# PowerDelivery.net
KiCad netlist of a schematic drawn in Altium Designer
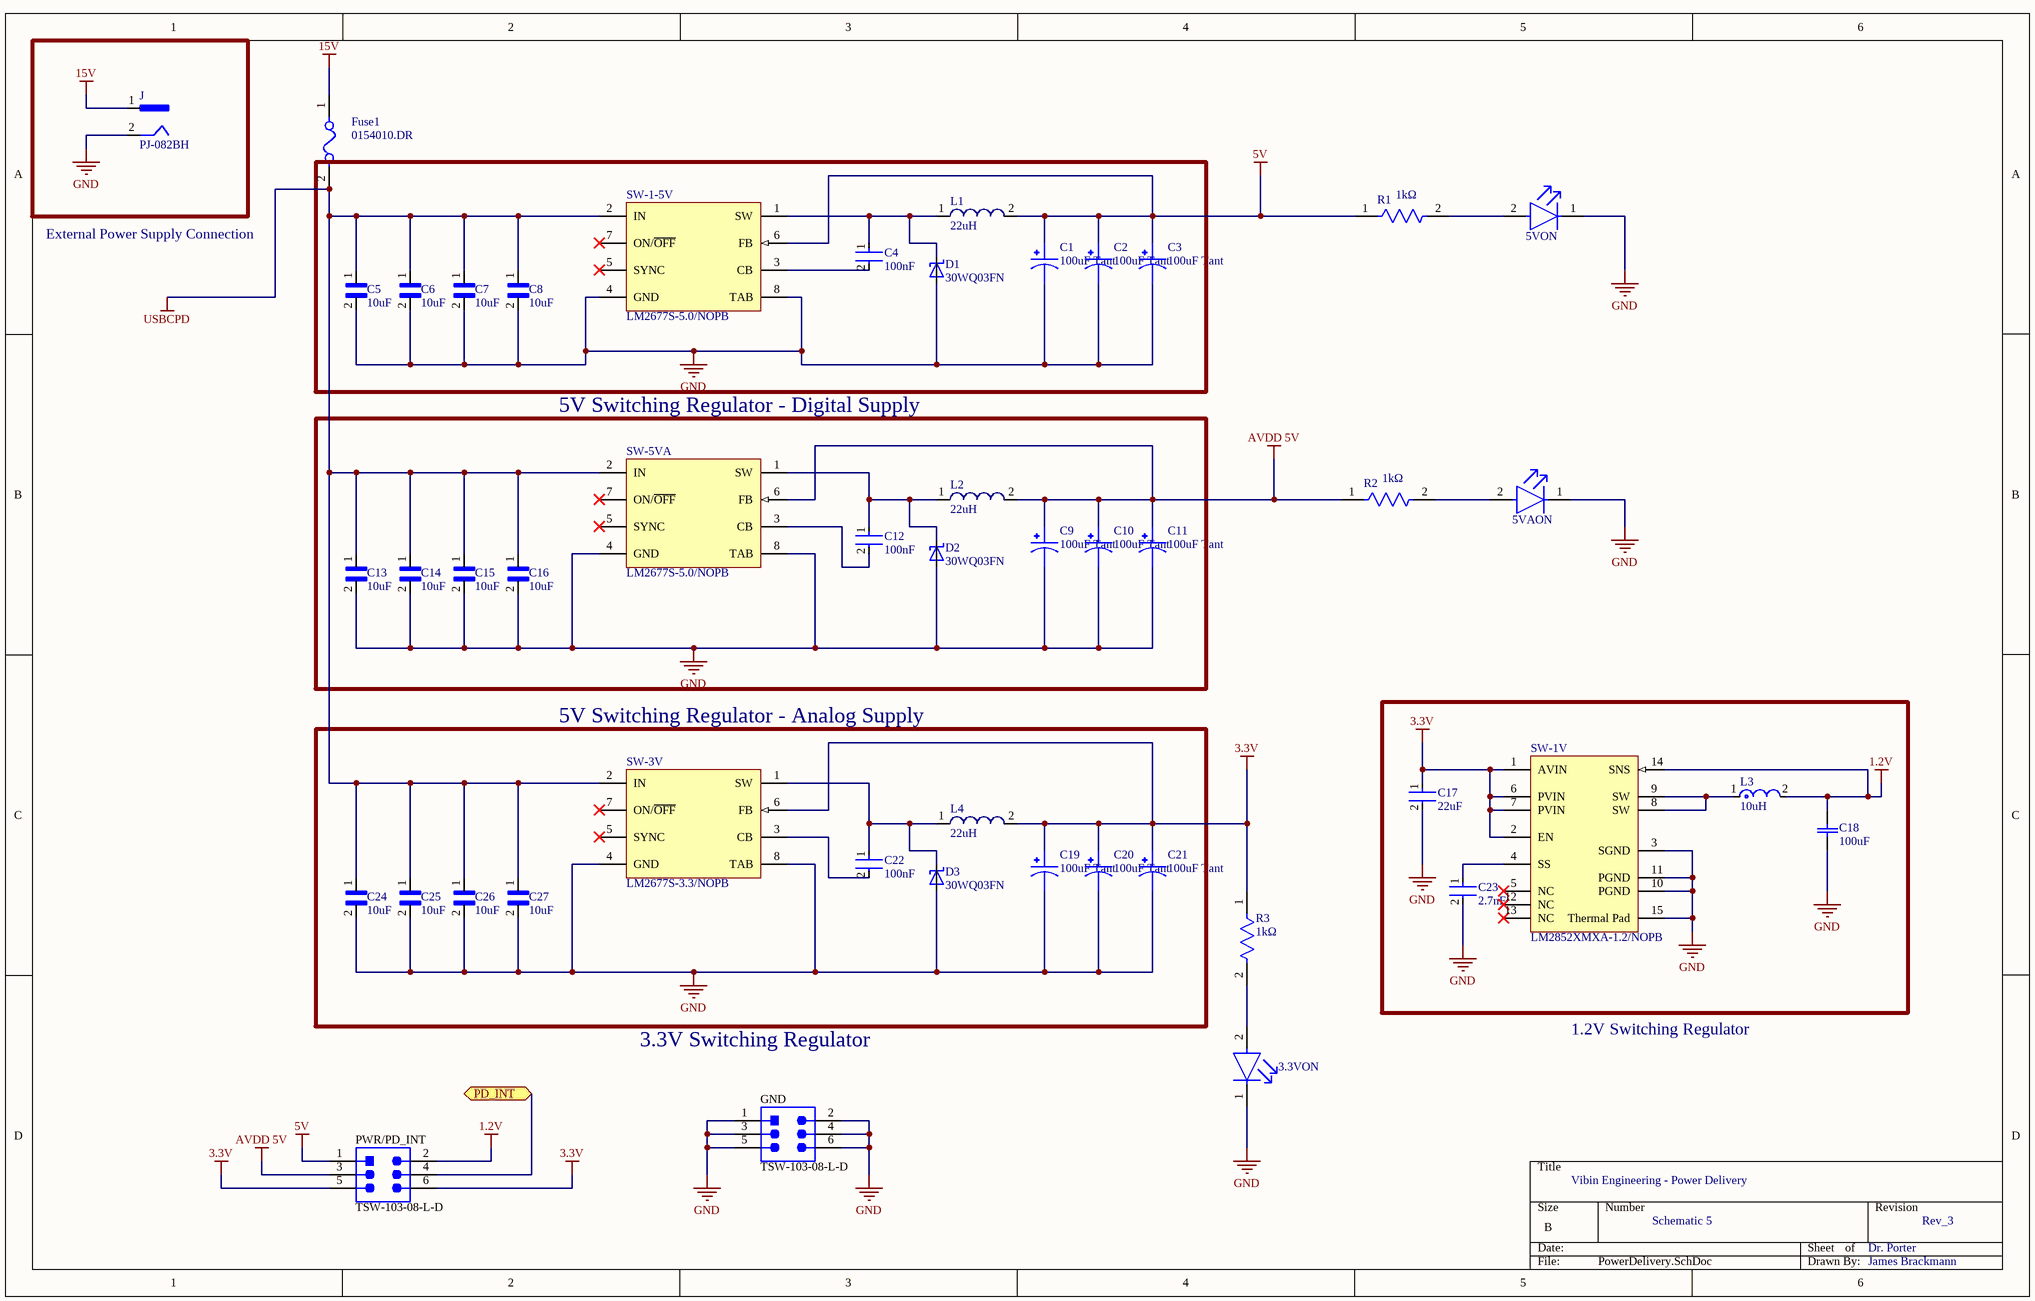
[diagram p0: PowerDelivery.SchDoc]

(export (version "E")
  (design (tool "Eeschema 10.0.6"))
  (components
    (comp (ref "3.3VON")
      (value "LTST-C190GKT")
      (footprint "FP-LTST-C190GKT-MFG")
      (description "LED GREEN CLEAR CHIP SMD       LTST-C190GKT")
      (fields (field (name "VOLTAGE") "2V"))
      (libsource (lib "Altium Content Vault") (part "8706943c75ba83719d021d2fdc84c58"))
    )
    (comp (ref "5VAON")
      (value "LTST-C190GKT")
      (footprint "FP-LTST-C190GKT-MFG")
      (description "LED GREEN CLEAR CHIP SMD       LTST-C190GKT")
      (fields (field (name "VOLTAGE") "2V"))
      (libsource (lib "Altium Content Vault") (part "8706943c75ba83719d021d2fdc84c58"))
    )
    (comp (ref "5VON")
      (value "LTST-C190GKT")
      (footprint "FP-LTST-C190GKT-MFG")
      (description "LED GREEN CLEAR CHIP SMD       LTST-C190GKT")
      (fields (field (name "VOLTAGE") "2V"))
      (libsource (lib "Altium Content Vault") (part "8706943c75ba83719d021d2fdc84c58"))
    )
    (comp (ref "C1")
      (value "100uF Tant")
      (footprint "CAPPM7343X310N")
      (description "100 碌F Molded Tantalum Capacitors 10 V 2917 (7343 Metric) 65mOhm      \r\nTPSD107K010R0065")
      (fields (field (name "MF") "AVX") (field (name "MP") "TPSD107K010R0065"))
      (libsource (lib "TPSD107K010R0065") (part "TPSD107K010R0065"))
    )
    (comp (ref "C2")
      (value "100uF Tant")
      (footprint "CAPPM7343X310N")
      (description "100 ÂµF Molded Tantalum Capacitors 10 V 2917 (7343 Metric) 65mOhm")
      (fields (field (name "MF") "AVX") (field (name "MP") "TPSD107K010R0065"))
      (libsource (lib "TPSD107K010R0065") (part "TPSD107K010R0065"))
    )
    (comp (ref "C3")
      (value "100uF Tant")
      (footprint "CAPPM7343X310N")
      (description "100 ÂµF Molded Tantalum Capacitors 10 V 2917 (7343 Metric) 65mOhm")
      (fields (field (name "MF") "AVX") (field (name "MP") "TPSD107K010R0065"))
      (libsource (lib "TPSD107K010R0065") (part "TPSD107K010R0065"))
    )
    (comp (ref "C4")
      (value "100nF")
      (footprint "FP-CC0603-DA-MFG")
      (description "CAP CER 10000PF 50V X7R 0603      CC0603KRX7R9BB103")
      (fields (field (name "TOLERANCE") "0.1") (field (name "MANUFACTURER PART NUMBER") "CC0603KRX7R9BB103"))
      (libsource (lib "Altium Content Vault") (part "11868f565c42a9108669ba33697ecf6"))
    )
    (comp (ref "C5")
      (value "10uF")
      (footprint "CAPPM7343X310N")
      (fields (field (name "MF") "Kemet") (field (name "MP") "T495D106M035ATE300"))
      (libsource (lib "T495D106M035ATE300") (part "T495D106M035ATE300"))
    )
    (comp (ref "C6")
      (value "10uF")
      (footprint "CAPPM7343X310N")
      (fields (field (name "MF") "Kemet") (field (name "MP") "T495D106M035ATE300"))
      (libsource (lib "T495D106M035ATE300") (part "T495D106M035ATE300"))
    )
    (comp (ref "C7")
      (value "10uF")
      (footprint "CAPPM7343X310N")
      (fields (field (name "MF") "Kemet") (field (name "MP") "T495D106M035ATE300"))
      (libsource (lib "T495D106M035ATE300") (part "T495D106M035ATE300"))
    )
    (comp (ref "C8")
      (value "10uF")
      (footprint "CAPPM7343X310N")
      (fields (field (name "MF") "Kemet") (field (name "MP") "T495D106M035ATE300"))
      (libsource (lib "T495D106M035ATE300") (part "T495D106M035ATE300"))
    )
    (comp (ref "C9")
      (value "100uF Tant")
      (footprint "CAPPM7343X310N")
      (description "100 碌F Molded Tantalum Capacitors 10 V 2917 (7343 Metric) 65mOhm      \r\nTPSD107K010R0065")
      (fields (field (name "MF") "AVX") (field (name "MP") "TPSD107K010R0065"))
      (libsource (lib "TPSD107K010R0065") (part "TPSD107K010R0065"))
    )
    (comp (ref "C10")
      (value "100uF Tant")
      (footprint "CAPPM7343X310N")
      (description "100 ÂµF Molded Tantalum Capacitors 10 V 2917 (7343 Metric) 65mOhm")
      (fields (field (name "MF") "AVX") (field (name "MP") "TPSD107K010R0065"))
      (libsource (lib "TPSD107K010R0065") (part "TPSD107K010R0065"))
    )
    (comp (ref "C11")
      (value "100uF Tant")
      (footprint "CAPPM7343X310N")
      (description "100 ÂµF Molded Tantalum Capacitors 10 V 2917 (7343 Metric) 65mOhm")
      (fields (field (name "MF") "AVX") (field (name "MP") "TPSD107K010R0065"))
      (libsource (lib "TPSD107K010R0065") (part "TPSD107K010R0065"))
    )
    (comp (ref "C12")
      (value "100nF")
      (footprint "FP-CC0603-DA-MFG")
      (description "CAP CER 10000PF 50V X7R 0603      CC0603KRX7R9BB103")
      (fields (field (name "TOLERANCE") "0.1") (field (name "MANUFACTURER PART NUMBER") "CC0603KRX7R9BB103"))
      (libsource (lib "Altium Content Vault") (part "11868f565c42a9108669ba33697ecf6"))
    )
    (comp (ref "C13")
      (value "10uF")
      (footprint "CAPPM7343X310N")
      (fields (field (name "MF") "Kemet") (field (name "MP") "T495D106M035ATE300"))
      (libsource (lib "T495D106M035ATE300") (part "T495D106M035ATE300"))
    )
    (comp (ref "C14")
      (value "10uF")
      (footprint "CAPPM7343X310N")
      (fields (field (name "MF") "Kemet") (field (name "MP") "T495D106M035ATE300"))
      (libsource (lib "T495D106M035ATE300") (part "T495D106M035ATE300"))
    )
    (comp (ref "C15")
      (value "10uF")
      (footprint "CAPPM7343X310N")
      (fields (field (name "MF") "Kemet") (field (name "MP") "T495D106M035ATE300"))
      (libsource (lib "T495D106M035ATE300") (part "T495D106M035ATE300"))
    )
    (comp (ref "C16")
      (value "10uF")
      (footprint "CAPPM7343X310N")
      (fields (field (name "MF") "Kemet") (field (name "MP") "T495D106M035ATE300"))
      (libsource (lib "T495D106M035ATE300") (part "T495D106M035ATE300"))
    )
    (comp (ref "C17")
      (value "22uF")
      (footprint "FP-GRM21B-0_15-MFG")
      (fields (field (name "VOLTAGE") "6.3V") (field (name "TOLERANCE") "20%"))
      (libsource (lib "Altium Content Vault") (part "b4654b650e69147ec39a6b967a45e02"))
    )
    (comp (ref "C18")
      (value "100uF")
      (footprint "CAPCP3216X180N")
      (fields (field (name "MP") "TCJA107M004R0200") (field (name "MF") "AVX"))
      (libsource (lib "TCJA107M004R0200") (part "TCJA107M004R0200"))
    )
    (comp (ref "C19")
      (value "100uF Tant")
      (footprint "CAPPM7343X310N")
      (description "100 碌F Molded Tantalum Capacitors 10 V 2917 (7343 Metric) 65mOhm      \r\nTPSD107K010R0065")
      (fields (field (name "MF") "AVX") (field (name "MP") "TPSD107K010R0065"))
      (libsource (lib "TPSD107K010R0065") (part "TPSD107K010R0065"))
    )
    (comp (ref "C20")
      (value "100uF Tant")
      (footprint "CAPPM7343X310N")
      (description "100 ÂµF Molded Tantalum Capacitors 10 V 2917 (7343 Metric) 65mOhm")
      (fields (field (name "MF") "AVX") (field (name "MP") "TPSD107K010R0065"))
      (libsource (lib "TPSD107K010R0065") (part "TPSD107K010R0065"))
    )
    (comp (ref "C21")
      (value "100uF Tant")
      (footprint "CAPPM7343X310N")
      (description "100 ÂµF Molded Tantalum Capacitors 10 V 2917 (7343 Metric) 65mOhm")
      (fields (field (name "MF") "AVX") (field (name "MP") "TPSD107K010R0065"))
      (libsource (lib "TPSD107K010R0065") (part "TPSD107K010R0065"))
    )
    (comp (ref "C22")
      (value "100nF")
      (footprint "FP-CC0603-DA-MFG")
      (description "CAP CER 10000PF 50V X7R 0603      CC0603KRX7R9BB103")
      (fields (field (name "TOLERANCE") "0.1") (field (name "MANUFACTURER PART NUMBER") "CC0603KRX7R9BB103"))
      (libsource (lib "Altium Content Vault") (part "11868f565c42a9108669ba33697ecf6"))
    )
    (comp (ref "C23")
      (value "2.7nF")
      (footprint "FP-C0402-BB-MFG")
      (description "C0402 2,700 pF X7R 5.00% 10 V        C0402C272J8RACAUTO")
      (fields
        (field (name "OCTOPART") "https://octopart.com/c0402c272j8racauto-kemet-16435644")
        (field (name "MANUFACTURER PART NUMBER") "C0402C272J8RACAUTO")
      )
      (libsource (lib "Altium Content Vault") (part "b4654b650e69147ec39a6b967a45e02"))
    )
    (comp (ref "C24")
      (value "10uF")
      (footprint "CAPPM7343X310N")
      (fields (field (name "MF") "Kemet") (field (name "MP") "T495D106M035ATE300"))
      (libsource (lib "T495D106M035ATE300") (part "T495D106M035ATE300"))
    )
    (comp (ref "C25")
      (value "10uF")
      (footprint "CAPPM7343X310N")
      (fields (field (name "MF") "Kemet") (field (name "MP") "T495D106M035ATE300"))
      (libsource (lib "T495D106M035ATE300") (part "T495D106M035ATE300"))
    )
    (comp (ref "C26")
      (value "10uF")
      (footprint "CAPPM7343X310N")
      (fields (field (name "MF") "Kemet") (field (name "MP") "T495D106M035ATE300"))
      (libsource (lib "T495D106M035ATE300") (part "T495D106M035ATE300"))
    )
    (comp (ref "C27")
      (value "10uF")
      (footprint "CAPPM7343X310N")
      (fields (field (name "MF") "Kemet") (field (name "MP") "T495D106M035ATE300"))
      (libsource (lib "T495D106M035ATE300") (part "T495D106M035ATE300"))
    )
    (comp (ref "D1")
      (value "30WQ03FN")
      (footprint "TO-252AA")
      (description "DIODE SCHOTTKY 30V 3.5A DPAK        30WQ03FN")
      (fields (field (name "MF") "Vishay Semiconductor Diodes Division"))
      (libsource (lib "30WQ03FN") (part "30WQ03FN"))
    )
    (comp (ref "D2")
      (value "30WQ03FN")
      (footprint "TO-252AA")
      (description "DIODE SCHOTTKY 30V 3.5A DPAK        30WQ03FN")
      (fields (field (name "MF") "Vishay Semiconductor Diodes Division"))
      (libsource (lib "30WQ03FN") (part "30WQ03FN"))
    )
    (comp (ref "D3")
      (value "30WQ03FN")
      (footprint "TO-252AA")
      (description "DIODE SCHOTTKY 30V 3.5A DPAK        30WQ03FN")
      (fields (field (name "MF") "Vishay Semiconductor Diodes Division"))
      (libsource (lib "30WQ03FN") (part "30WQ03FN"))
    )
    (comp (ref "Fuse1")
      (value "0154010.DR")
      (footprint "FP-0154-MFG")
      (description "FUSE BRD MNT 10A 125VAC/VDC SMD    0154010.DR")
      (fields
        (field (name "MANUFACTURER") "Littelfuse Inc")
        (field (name "OCTOPART") "https://octopart.com/0154010.dr-littelfuse-565890")
      )
      (libsource (lib "Altium Content Vault") (part "5bcf9b9f640e542cf0359d10258e979"))
    )
    (comp (ref "GND")
      (value "TSW-103-08-L-D")
      (footprint "SMTC-TSW-103-08-L-D_V")
      (fields (field (name "MANUFACTURER") "Samtec"))
      (libsource (lib "Altium Content Vault") (part "CN-2P-M-R6"))
    )
    (comp (ref "J")
      (value "PJ-082BH")
      (footprint "CUI_PJ-082BH")
      (description "2.5 x 6.5 mm, 10.0 A, Horizontal, Through Hole, Shielded, Dc Power Jack Connector")
      (fields (field (name "MF") "CUI Devices"))
      (libsource (lib "PJ-082BH") (part "PJ-082BH"))
    )
    (comp (ref "L1")
      (value "22uH")
      (footprint "WE-PD2SR 7850")
      (description "Shielded Power Inductor WE-PD2SR, L=22.0 µH     744787220")
      (fields (field (name "PARTNUMBER") "744787220") (field (name "MANUFACTURER") "Wuerth Elektronik"))
      (libsource (lib "Altium Content Vault") (part "WE-IND-INDUCTOR-2"))
    )
    (comp (ref "L2")
      (value "22uH")
      (footprint "WE-PD2SR 7850")
      (description "Shielded Power Inductor WE-PD2SR, L=22.0 µH     744787220")
      (fields (field (name "PARTNUMBER") "744787220") (field (name "MANUFACTURER") "Wuerth Elektronik"))
      (libsource (lib "Altium Content Vault") (part "WE-IND-INDUCTOR-2"))
    )
    (comp (ref "L3")
      (value "10uH")
      (footprint "FP-DEM8045C-MFG")
      (description "Shielded Wirewound Inductor 10uH 20% 3900mA 0.0396Ω SMD     DEM8045Z-100M=P3")
      (libsource (lib "Altium Content Vault") (part "4cc4b267dca4c8e51f7102f422741d8"))
    )
    (comp (ref "L4")
      (value "22uH")
      (footprint "WE-PD2SR 7850")
      (description "Shielded Power Inductor WE-PD2SR, L=22.0 µH     744787220")
      (fields (field (name "PARTNUMBER") "744787220") (field (name "MANUFACTURER") "Wuerth Elektronik"))
      (libsource (lib "Altium Content Vault") (part "WE-IND-INDUCTOR-2"))
    )
    (comp (ref "PWR/PD_INT")
      (value "TSW-103-08-L-D")
      (footprint "SMTC-TSW-103-08-L-D_V")
      (fields (field (name "MANUFACTURER") "Samtec"))
      (libsource (lib "Altium Content Vault") (part "CN-2P-M-R6"))
    )
    (comp (ref "R1")
      (value "1kΩ")
      (footprint "FP-CRCW0603-e3-MFG")
      (description "RES Thick Film, 1kΩ, 1%, 0.1W, 100ppm/°C, 0603")
      (fields (field (name "TOLERANCE") "1%"))
      (libsource (lib "Altium Content Vault") (part "1029c3af85768c4190bb7ad29bc67b5"))
    )
    (comp (ref "R2")
      (value "1kΩ")
      (footprint "FP-CRCW0603-e3-MFG")
      (description "RES Thick Film, 1kΩ, 1%, 0.1W, 100ppm/°C, 0603")
      (fields (field (name "TOLERANCE") "1%"))
      (libsource (lib "Altium Content Vault") (part "1029c3af85768c4190bb7ad29bc67b5"))
    )
    (comp (ref "R3")
      (value "1kΩ")
      (footprint "FP-CRCW0603-e3-MFG")
      (description "RES Thick Film, 1kΩ, 1%, 0.1W, 100ppm/°C, 0603")
      (fields (field (name "TOLERANCE") "1%"))
      (libsource (lib "Altium Content Vault") (part "1029c3af85768c4190bb7ad29bc67b5"))
    )
    (comp (ref "SW-1-5V")
      (value "LM2677S-5.0/NOPB")
      (footprint "KTW0007B_N")
      (fields (field (name "MANUFACTURER") "Texas Instruments"))
      (libsource (lib "Altium Content Vault") (part "PM-REG-LM2670S-12"))
    )
    (comp (ref "SW-1V")
      (value "LM2852XMXA-1.2/NOPB")
      (footprint "MXA14A_M")
      (fields (field (name "MANUFACTURER") "National Semiconductor"))
      (libsource (lib "Altium Content Vault") (part "PM-REG-LM2852"))
    )
    (comp (ref "SW-3V")
      (value "LM2677S-3.3/NOPB")
      (footprint "KTW0007B_M")
      (fields (field (name "MANUFACTURER") "Texas Instruments"))
      (libsource (lib "Altium Content Vault") (part "PM-REG-LM2670S-12"))
    )
    (comp (ref "SW-5VA")
      (value "LM2677S-5.0/NOPB")
      (footprint "KTW0007B_N")
      (fields (field (name "MANUFACTURER") "Texas Instruments"))
      (libsource (lib "Altium Content Vault") (part "PM-REG-LM2670S-12"))
    )
  )
  (nets
    (net (code "1") (name "/PD_INT") (class "Default")
      (node (ref "PWR/PD_INT") (pin "4") (pinfunction "4_4") (pintype "passive"))
    )
    (net (code "2") (name "1.2V") (class "Default")
      (node (ref "C18") (pin "2") (pinfunction "C2_2") (pintype "passive"))
      (node (ref "L3") (pin "2") (pinfunction "2_2") (pintype "passive"))
      (node (ref "PWR/PD_INT") (pin "2") (pinfunction "2_2") (pintype "passive"))
      (node (ref "SW-1V") (pin "14") (pinfunction "SNS_14") (pintype "input"))
    )
    (net (code "3") (name "3.3V") (class "Default")
      (node (ref "C17") (pin "1") (pinfunction "1_1") (pintype "passive"))
      (node (ref "C19") (pin "1") (pinfunction "1_1") (pintype "passive"))
      (node (ref "C20") (pin "1") (pinfunction "1_1") (pintype "passive"))
      (node (ref "C21") (pin "1") (pinfunction "1_1") (pintype "passive"))
      (node (ref "L4") (pin "2") (pinfunction "2_2") (pintype "passive"))
      (node (ref "PWR/PD_INT") (pin "5") (pinfunction "5_5") (pintype "passive"))
      (node (ref "PWR/PD_INT") (pin "6") (pinfunction "6_6") (pintype "passive"))
      (node (ref "R3") (pin "1") (pinfunction "1_1") (pintype "passive"))
      (node (ref "SW-1V") (pin "1") (pinfunction "AVIN_1") (pintype "power_in"))
      (node (ref "SW-1V") (pin "2") (pinfunction "EN_2") (pintype "passive"))
      (node (ref "SW-1V") (pin "6") (pinfunction "PVIN_6") (pintype "power_in"))
      (node (ref "SW-1V") (pin "7") (pinfunction "PVIN_7") (pintype "power_in"))
      (node (ref "SW-3V") (pin "6") (pinfunction "FB_6") (pintype "input"))
    )
    (net (code "4") (name "5V") (class "Default")
      (node (ref "C1") (pin "1") (pinfunction "1_1") (pintype "passive"))
      (node (ref "C2") (pin "1") (pinfunction "1_1") (pintype "passive"))
      (node (ref "C3") (pin "1") (pinfunction "1_1") (pintype "passive"))
      (node (ref "L1") (pin "2") (pinfunction "2_2") (pintype "passive"))
      (node (ref "PWR/PD_INT") (pin "1") (pinfunction "1_1") (pintype "passive"))
      (node (ref "R1") (pin "1") (pinfunction "1_1") (pintype "passive"))
      (node (ref "SW-1-5V") (pin "6") (pinfunction "FB_6") (pintype "input"))
    )
    (net (code "5") (name "15V") (class "Default")
      (node (ref "Fuse1") (pin "1") (pinfunction "1_1") (pintype "passive"))
      (node (ref "J") (pin "1") (pinfunction "1_1") (pintype "passive"))
    )
    (net (code "6") (name "AVDD 5V") (class "Default")
      (node (ref "C10") (pin "1") (pinfunction "1_1") (pintype "passive"))
      (node (ref "C11") (pin "1") (pinfunction "1_1") (pintype "passive"))
      (node (ref "C9") (pin "1") (pinfunction "1_1") (pintype "passive"))
      (node (ref "L2") (pin "2") (pinfunction "2_2") (pintype "passive"))
      (node (ref "PWR/PD_INT") (pin "3") (pinfunction "3_3") (pintype "passive"))
      (node (ref "R2") (pin "1") (pinfunction "1_1") (pintype "passive"))
      (node (ref "SW-5VA") (pin "6") (pinfunction "FB_6") (pintype "input"))
    )
    (net (code "7") (name "GND") (class "Default")
      (node (ref "3.3VON") (pin "1") (pinfunction "C_1") (pintype "passive"))
      (node (ref "5VAON") (pin "1") (pinfunction "C_1") (pintype "passive"))
      (node (ref "5VON") (pin "1") (pinfunction "C_1") (pintype "passive"))
      (node (ref "C1") (pin "2") (pinfunction "2_2") (pintype "passive"))
      (node (ref "C10") (pin "2") (pinfunction "2_2") (pintype "passive"))
      (node (ref "C11") (pin "2") (pinfunction "2_2") (pintype "passive"))
      (node (ref "C13") (pin "2") (pinfunction "2_2") (pintype "passive"))
      (node (ref "C14") (pin "2") (pinfunction "2_2") (pintype "passive"))
      (node (ref "C15") (pin "2") (pinfunction "2_2") (pintype "passive"))
      (node (ref "C16") (pin "2") (pinfunction "2_2") (pintype "passive"))
      (node (ref "C17") (pin "2") (pinfunction "2_2") (pintype "passive"))
      (node (ref "C18") (pin "1") (pinfunction "C1_1") (pintype "passive"))
      (node (ref "C19") (pin "2") (pinfunction "2_2") (pintype "passive"))
      (node (ref "C2") (pin "2") (pinfunction "2_2") (pintype "passive"))
      (node (ref "C20") (pin "2") (pinfunction "2_2") (pintype "passive"))
      (node (ref "C21") (pin "2") (pinfunction "2_2") (pintype "passive"))
      (node (ref "C23") (pin "2") (pinfunction "2_2") (pintype "passive"))
      (node (ref "C24") (pin "2") (pinfunction "2_2") (pintype "passive"))
      (node (ref "C25") (pin "2") (pinfunction "2_2") (pintype "passive"))
      (node (ref "C26") (pin "2") (pinfunction "2_2") (pintype "passive"))
      (node (ref "C27") (pin "2") (pinfunction "2_2") (pintype "passive"))
      (node (ref "C3") (pin "2") (pinfunction "2_2") (pintype "passive"))
      (node (ref "C5") (pin "2") (pinfunction "2_2") (pintype "passive"))
      (node (ref "C6") (pin "2") (pinfunction "2_2") (pintype "passive"))
      (node (ref "C7") (pin "2") (pinfunction "2_2") (pintype "passive"))
      (node (ref "C8") (pin "2") (pinfunction "2_2") (pintype "passive"))
      (node (ref "C9") (pin "2") (pinfunction "2_2") (pintype "passive"))
      (node (ref "D1") (pin "1") (pinfunction "A1_1") (pintype "passive"))
      (node (ref "D2") (pin "1") (pinfunction "A1_1") (pintype "passive"))
      (node (ref "D3") (pin "1") (pinfunction "A1_1") (pintype "passive"))
      (node (ref "GND") (pin "1") (pinfunction "1_1") (pintype "passive"))
      (node (ref "GND") (pin "2") (pinfunction "2_2") (pintype "passive"))
      (node (ref "GND") (pin "3") (pinfunction "3_3") (pintype "passive"))
      (node (ref "GND") (pin "4") (pinfunction "4_4") (pintype "passive"))
      (node (ref "GND") (pin "5") (pinfunction "5_5") (pintype "passive"))
      (node (ref "GND") (pin "6") (pinfunction "6_6") (pintype "passive"))
      (node (ref "J") (pin "2") (pinfunction "2_2") (pintype "passive"))
      (node (ref "SW-1-5V") (pin "4") (pinfunction "GND_4") (pintype "power_in"))
      (node (ref "SW-1-5V") (pin "8") (pinfunction "TAB_8") (pintype "passive"))
      (node (ref "SW-1V") (pin "10") (pinfunction "PGND_10") (pintype "power_in"))
      (node (ref "SW-1V") (pin "11") (pinfunction "PGND_11") (pintype "power_in"))
      (node (ref "SW-1V") (pin "15") (pinfunction "Thermal_Pad_15") (pintype "power_in"))
      (node (ref "SW-1V") (pin "3") (pinfunction "SGND_3") (pintype "power_in"))
      (node (ref "SW-3V") (pin "4") (pinfunction "GND_4") (pintype "power_in"))
      (node (ref "SW-3V") (pin "8") (pinfunction "TAB_8") (pintype "passive"))
      (node (ref "SW-5VA") (pin "4") (pinfunction "GND_4") (pintype "power_in"))
      (node (ref "SW-5VA") (pin "8") (pinfunction "TAB_8") (pintype "passive"))
    )
    (net (code "8") (name "Net-(3.3VON-A)") (class "Default")
      (node (ref "3.3VON") (pin "2") (pinfunction "A_2") (pintype "passive"))
      (node (ref "R3") (pin "2") (pinfunction "2_2") (pintype "passive"))
    )
    (net (code "9") (name "Net-(5VAON-A)") (class "Default")
      (node (ref "5VAON") (pin "2") (pinfunction "A_2") (pintype "passive"))
      (node (ref "R2") (pin "2") (pinfunction "2_2") (pintype "passive"))
    )
    (net (code "10") (name "Net-(5VON-A)") (class "Default")
      (node (ref "5VON") (pin "2") (pinfunction "A_2") (pintype "passive"))
      (node (ref "R1") (pin "2") (pinfunction "2_2") (pintype "passive"))
    )
    (net (code "11") (name "Net-(D1-C)") (class "Default")
      (node (ref "C4") (pin "1") (pinfunction "1_1") (pintype "passive"))
      (node (ref "D1") (pin "3") (pinfunction "C_3") (pintype "passive"))
      (node (ref "L1") (pin "1") (pinfunction "1_1") (pintype "passive"))
      (node (ref "SW-1-5V") (pin "1") (pinfunction "SW_1") (pintype "power_in"))
    )
    (net (code "12") (name "Net-(D2-C)") (class "Default")
      (node (ref "C12") (pin "1") (pinfunction "1_1") (pintype "passive"))
      (node (ref "D2") (pin "3") (pinfunction "C_3") (pintype "passive"))
      (node (ref "L2") (pin "1") (pinfunction "1_1") (pintype "passive"))
      (node (ref "SW-5VA") (pin "1") (pinfunction "SW_1") (pintype "power_in"))
    )
    (net (code "13") (name "Net-(D3-C)") (class "Default")
      (node (ref "C22") (pin "1") (pinfunction "1_1") (pintype "passive"))
      (node (ref "D3") (pin "3") (pinfunction "C_3") (pintype "passive"))
      (node (ref "L4") (pin "1") (pinfunction "1_1") (pintype "passive"))
      (node (ref "SW-3V") (pin "1") (pinfunction "SW_1") (pintype "power_in"))
    )
    (net (code "14") (name "Net-(L3-Pad1)") (class "Default")
      (node (ref "L3") (pin "1") (pinfunction "1_1") (pintype "passive"))
      (node (ref "SW-1V") (pin "8") (pinfunction "SW_8") (pintype "power_in"))
      (node (ref "SW-1V") (pin "9") (pinfunction "SW_9") (pintype "power_in"))
    )
    (net (code "15") (name "Net-(SW-1-5V-CB)") (class "Default")
      (node (ref "C4") (pin "2") (pinfunction "2_2") (pintype "passive"))
      (node (ref "SW-1-5V") (pin "3") (pinfunction "CB_3") (pintype "passive"))
    )
    (net (code "16") (name "Net-(SW-1V-SS)") (class "Default")
      (node (ref "C23") (pin "1") (pinfunction "1_1") (pintype "passive"))
      (node (ref "SW-1V") (pin "4") (pinfunction "SS_4") (pintype "passive"))
    )
    (net (code "17") (name "Net-(SW-3V-CB)") (class "Default")
      (node (ref "C22") (pin "2") (pinfunction "2_2") (pintype "passive"))
      (node (ref "SW-3V") (pin "3") (pinfunction "CB_3") (pintype "passive"))
    )
    (net (code "18") (name "Net-(SW-5VA-CB)") (class "Default")
      (node (ref "C12") (pin "2") (pinfunction "2_2") (pintype "passive"))
      (node (ref "SW-5VA") (pin "3") (pinfunction "CB_3") (pintype "passive"))
    )
    (net (code "19") (name "USBCPD") (class "Default")
      (node (ref "C13") (pin "1") (pinfunction "1_1") (pintype "passive"))
      (node (ref "C14") (pin "1") (pinfunction "1_1") (pintype "passive"))
      (node (ref "C15") (pin "1") (pinfunction "1_1") (pintype "passive"))
      (node (ref "C16") (pin "1") (pinfunction "1_1") (pintype "passive"))
      (node (ref "C24") (pin "1") (pinfunction "1_1") (pintype "passive"))
      (node (ref "C25") (pin "1") (pinfunction "1_1") (pintype "passive"))
      (node (ref "C26") (pin "1") (pinfunction "1_1") (pintype "passive"))
      (node (ref "C27") (pin "1") (pinfunction "1_1") (pintype "passive"))
      (node (ref "C5") (pin "1") (pinfunction "1_1") (pintype "passive"))
      (node (ref "C6") (pin "1") (pinfunction "1_1") (pintype "passive"))
      (node (ref "C7") (pin "1") (pinfunction "1_1") (pintype "passive"))
      (node (ref "C8") (pin "1") (pinfunction "1_1") (pintype "passive"))
      (node (ref "Fuse1") (pin "2") (pinfunction "2_2") (pintype "passive"))
      (node (ref "SW-1-5V") (pin "2") (pinfunction "IN_2") (pintype "power_in"))
      (node (ref "SW-3V") (pin "2") (pinfunction "IN_2") (pintype "power_in"))
      (node (ref "SW-5VA") (pin "2") (pinfunction "IN_2") (pintype "power_in"))
    )
    (net (code "20") (name "unconnected-(D1-A2-Pad2)") (class "Default")
      (node (ref "D1") (pin "2") (pinfunction "A2_2") (pintype "passive"))
    )
    (net (code "21") (name "unconnected-(D2-A2-Pad2)") (class "Default")
      (node (ref "D2") (pin "2") (pinfunction "A2_2") (pintype "passive"))
    )
    (net (code "22") (name "unconnected-(D3-A2-Pad2)") (class "Default")
      (node (ref "D3") (pin "2") (pinfunction "A2_2") (pintype "passive"))
    )
    (net (code "23") (name "unconnected-(SW-1-5V-ON{slash}~{OFF}-Pad7)") (class "Default")
      (node (ref "SW-1-5V") (pin "7") (pinfunction "ON/~{OFF}_7") (pintype "passive+no_connect"))
    )
    (net (code "24") (name "unconnected-(SW-1-5V-SYNC-Pad5)") (class "Default")
      (node (ref "SW-1-5V") (pin "5") (pinfunction "SYNC_5") (pintype "passive+no_connect"))
    )
    (net (code "25") (name "unconnected-(SW-1V-NC-Pad5)") (class "Default")
      (node (ref "SW-1V") (pin "5") (pinfunction "NC_5") (pintype "passive+no_connect"))
    )
    (net (code "26") (name "unconnected-(SW-1V-NC-Pad12)") (class "Default")
      (node (ref "SW-1V") (pin "12") (pinfunction "NC_12") (pintype "passive+no_connect"))
    )
    (net (code "27") (name "unconnected-(SW-1V-NC-Pad13)") (class "Default")
      (node (ref "SW-1V") (pin "13") (pinfunction "NC_13") (pintype "passive+no_connect"))
    )
    (net (code "28") (name "unconnected-(SW-3V-ON{slash}~{OFF}-Pad7)") (class "Default")
      (node (ref "SW-3V") (pin "7") (pinfunction "ON/~{OFF}_7") (pintype "passive+no_connect"))
    )
    (net (code "29") (name "unconnected-(SW-3V-SYNC-Pad5)") (class "Default")
      (node (ref "SW-3V") (pin "5") (pinfunction "SYNC_5") (pintype "passive+no_connect"))
    )
    (net (code "30") (name "unconnected-(SW-5VA-ON{slash}~{OFF}-Pad7)") (class "Default")
      (node (ref "SW-5VA") (pin "7") (pinfunction "ON/~{OFF}_7") (pintype "passive+no_connect"))
    )
    (net (code "31") (name "unconnected-(SW-5VA-SYNC-Pad5)") (class "Default")
      (node (ref "SW-5VA") (pin "5") (pinfunction "SYNC_5") (pintype "passive+no_connect"))
    )
  )
)
